# Poactuator_Power_Circuits.net
KiCad netlist of a schematic drawn in Altium Designer
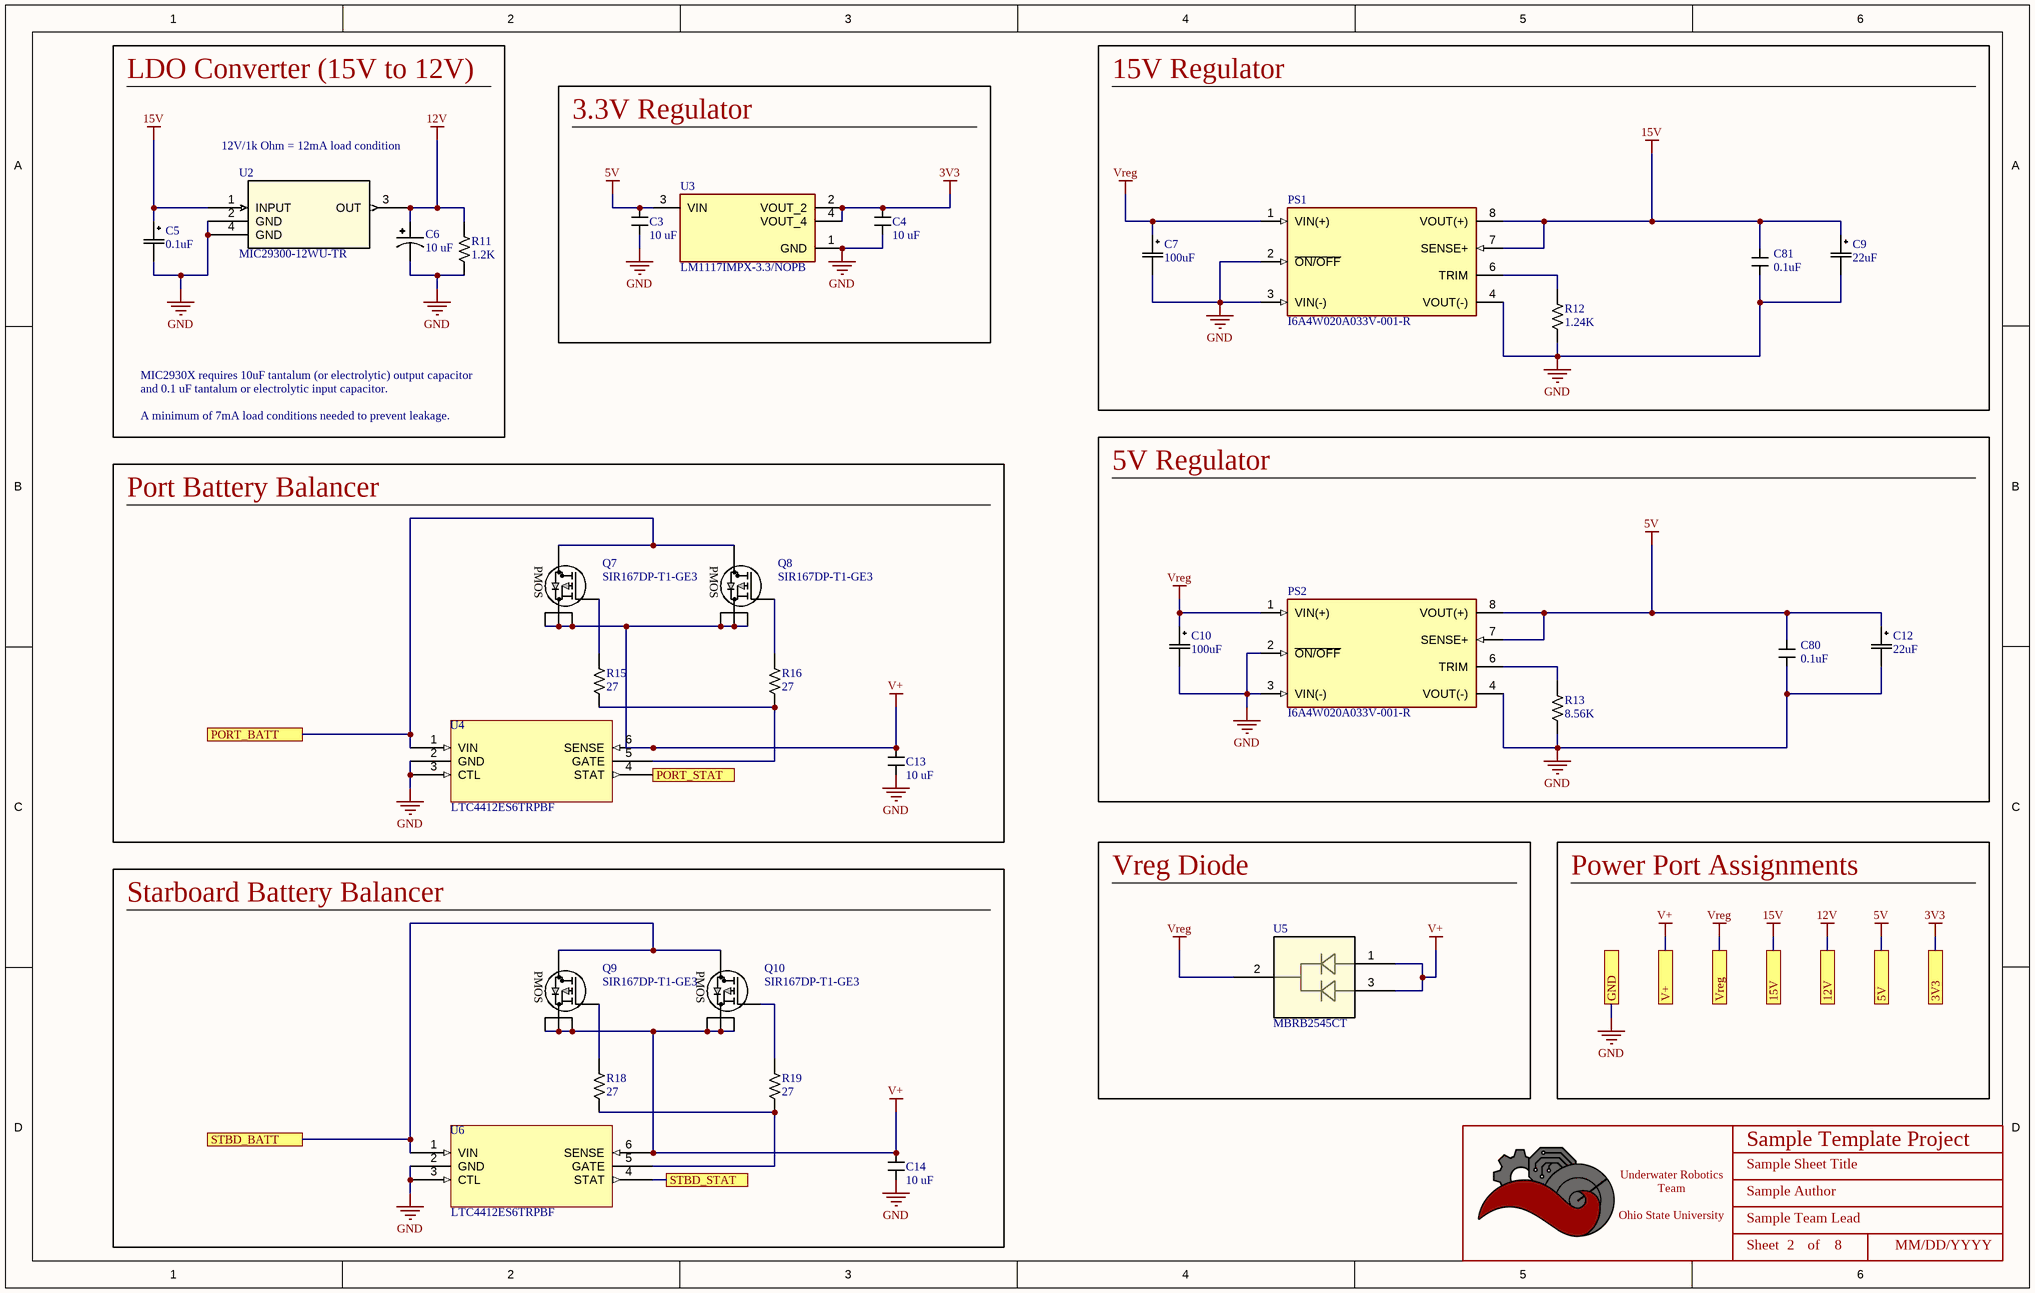
[diagram p0: Poactuator_Power_Circuits.SchDoc]

(export (version "E")
  (design (tool "Eeschema 10.0.6"))
  (components
    (comp (ref "C3")
      (value "10uF Ceramic 6.3V")
      (footprint "CAPACITOR_0603")
      (description "Cap 10uF 6.3V +/-20%\r\nCeramic 0603")
      (fields
        (field (name "TOLERANCE") "+/- 20%")
        (field (name "VOLTAGE") "6.3V")
        (field (name "VALUE (UF)") "10 uF")
        (field (name "MADE BY") "Flip B")
      )
      (libsource (lib "Capacitors") (part "CAPACITOR_10uF_0603"))
    )
    (comp (ref "C4")
      (value "10uF Ceramic 6.3V")
      (footprint "CAPACITOR_0603")
      (description "Cap 10uF 6.3V +/-20%\r\nCeramic 0603")
      (fields
        (field (name "TOLERANCE") "+/- 20%")
        (field (name "VOLTAGE") "6.3V")
        (field (name "VALUE (UF)") "10 uF")
        (field (name "MADE BY") "Flip B")
      )
      (libsource (lib "Capacitors") (part "CAPACITOR_10uF_0603"))
    )
    (comp (ref "C5")
      (value "0.1uF")
      (footprint "U2-D_NCH")
      (description "0.1 µF 35 V Aluminum Electrolytic Capacitors Radial, Can - SMD 7000 Hrs @ 105°C")
      (fields
        (field (name "MANUFACTURER_PART_NUMBER") "UCB1V0R1MCL1GS")
        (field (name "Comment") "0.1uF electrolytic 35 V")
        (field (name "COPYRIGHT") "Copyright (C) 2022 Ultra Librarian. All rights reserved.")
        (field (name "MADE BY") "Tyson Nguyen")
      )
      (libsource (lib "Capacitors") (part "CAP ALUM 0.1UF 20% 35V SMD"))
    )
    (comp (ref "C6")
      (value "10uF Tantalum 16V")
      (footprint "CAPACITOR_1206 - POLAR")
      (description "Cap 10uF 16V +/-20%\r\nTantalum 1206")
      (fields
        (field (name "TOLERANCE") "+/- 10%")
        (field (name "VOLTAGE") "16V")
        (field (name "VALUE (UF)") "10 uF")
        (field (name "MADE BY") "Dylan T")
      )
      (libsource (lib "Capacitors") (part "CAPACITOR_10uF_1206_Tantalum_1"))
    )
    (comp (ref "C7")
      (value "100uF")
      (footprint "PCAP_8x5.4-ELECT_NCA")
      (description "100 µF 35 V Aluminum Electrolytic Capacitors Radial, Can - SMD 1000 Hrs")
      (fields
        (field (name "MANUFACTURER_PART_NUMBER") "UCB1V0R1MCL1GS")
        (field (name "Comment") "100uF electrolytic 35 V")
        (field (name "COPYRIGHT") "Copyright (C) 2022 Ultra Librarian. All rights reserved.")
        (field (name "MADE BY") "Tyson Nguyen")
      )
      (libsource (lib "Capacitors") (part "CAP ALUM 100UF 20% 35V SMD"))
    )
    (comp (ref "C9")
      (value "22uF")
      (footprint "PCAP_8x5.4-ELECT_NCA")
      (description "22 µF 35 V Aluminum Electrolytic Capacitors Radial, Can - SMD 1000 Hrs")
      (fields
        (field (name "VOLTAGE") "35V")
        (field (name "Comment") "22uF electrolytic 35 V")
        (field (name "MADE BY") "Robert Pafford")
      )
      (libsource (lib "Capacitors") (part "CAP ALUM 22UF 20% 35V SMD"))
    )
    (comp (ref "C10")
      (value "100uF")
      (footprint "PCAP_8x5.4-ELECT_NCA")
      (description "100 µF 35 V Aluminum Electrolytic Capacitors Radial, Can - SMD 1000 Hrs")
      (fields
        (field (name "MANUFACTURER_PART_NUMBER") "UCB1V0R1MCL1GS")
        (field (name "Comment") "100uF electrolytic 35 V")
        (field (name "COPYRIGHT") "Copyright (C) 2022 Ultra Librarian. All rights reserved.")
        (field (name "MADE BY") "Tyson Nguyen")
      )
      (libsource (lib "Capacitors") (part "CAP ALUM 100UF 20% 35V SMD"))
    )
    (comp (ref "C12")
      (value "22uF")
      (footprint "PCAP_8x5.4-ELECT_NCA")
      (description "22 µF 35 V Aluminum Electrolytic Capacitors Radial, Can - SMD 1000 Hrs")
      (fields
        (field (name "VOLTAGE") "35V")
        (field (name "Comment") "22uF electrolytic 35 V")
        (field (name "MADE BY") "Robert Pafford")
      )
      (libsource (lib "Capacitors") (part "CAP ALUM 22UF 20% 35V SMD"))
    )
    (comp (ref "C13")
      (value "10uF Ceramic 25V")
      (footprint "CAPACITOR_1206")
      (description "Cap 10uF 25V +/-10%\r\nCeramic 1206")
      (fields
        (field (name "TOLERANCE") "+/- 10%")
        (field (name "VOLTAGE") "25V")
        (field (name "VALUE (UF)") "10 uF")
        (field (name "MADE BY") "Robert Pafford")
      )
      (libsource (lib "Capacitors") (part "CAPACITOR_10uF_1206"))
    )
    (comp (ref "C14")
      (value "10uF Ceramic 25V")
      (footprint "CAPACITOR_1206")
      (description "Cap 10uF 25V +/-10%\r\nCeramic 1206")
      (fields
        (field (name "TOLERANCE") "+/- 10%")
        (field (name "VOLTAGE") "25V")
        (field (name "VALUE (UF)") "10 uF")
        (field (name "MADE BY") "Robert Pafford")
      )
      (libsource (lib "Capacitors") (part "CAPACITOR_10uF_1206"))
    )
    (comp (ref "C80")
      (value "CL05A104KA5NNNC")
      (footprint "CL05A104KA5NNNC")
      (description "0.1 µF ±10% 25V Ceramic Capacitor X5R 0402 (1005 Metric)")
      (fields (field (name "CAPACITANCE") "0.1uF") (field (name "TOLERANCE") "+/- 10%"))
      (libsource (lib "Capacitors") (part "CAP CER 0.1UF 25V X5R 0402"))
    )
    (comp (ref "C81")
      (value "CL05A104KA5NNNC")
      (footprint "CL05A104KA5NNNC")
      (description "0.1 µF ±10% 25V Ceramic Capacitor X5R 0402 (1005 Metric)")
      (fields (field (name "CAPACITANCE") "0.1uF") (field (name "TOLERANCE") "+/- 10%"))
      (libsource (lib "Capacitors") (part "CAP CER 0.1UF 25V X5R 0402"))
    )
    (comp (ref "PS1")
      (value "I6A4W020A033V-001-R")
      (footprint "CONV_I6A4W020A033V-001-R")
      (description "Non-Isolated PoL Module DC DC Converter 1 Output 3.3 ~ 15V 20A 9V - 53V Input")
      (fields (field (name "MF") "TDK-Lambda Americas"))
      (libsource (lib "I6A4W020A033V-001-R") (part "I6A4W020A033V-001-R"))
    )
    (comp (ref "PS2")
      (value "I6A4W020A033V-001-R")
      (footprint "CONV_I6A4W020A033V-001-R")
      (description "Non-Isolated PoL Module DC DC Converter 1 Output 3.3 ~ 15V 20A 9V - 53V Input")
      (fields (field (name "MF") "TDK-Lambda Americas"))
      (libsource (lib "I6A4W020A033V-001-R") (part "I6A4W020A033V-001-R"))
    )
    (comp (ref "Q7")
      (value "SIR167DP-T1-GE3")
      (footprint "MOSFET_7DP-T1-GE3_VIS")
      (description "P-Channel 30 V 60A (Tc) 65.8W (Tc) Surface Mount PowerPAK® SO-8")
      (fields (field (name "COPYRIGHT") "Copyright (C) 2022 Ultra Librarian. All rights reserved."))
      (libsource (lib "Transistors") (part "SIR167DP-T1-GE3"))
    )
    (comp (ref "Q8")
      (value "SIR167DP-T1-GE3")
      (footprint "MOSFET_7DP-T1-GE3_VIS")
      (description "P-Channel 30 V 60A (Tc) 65.8W (Tc) Surface Mount PowerPAK® SO-8")
      (fields (field (name "COPYRIGHT") "Copyright (C) 2022 Ultra Librarian. All rights reserved."))
      (libsource (lib "Transistors") (part "SIR167DP-T1-GE3"))
    )
    (comp (ref "Q9")
      (value "SIR167DP-T1-GE3")
      (footprint "MOSFET_7DP-T1-GE3_VIS")
      (description "P-Channel 30 V 60A (Tc) 65.8W (Tc) Surface Mount PowerPAK® SO-8")
      (fields (field (name "COPYRIGHT") "Copyright (C) 2022 Ultra Librarian. All rights reserved."))
      (libsource (lib "Transistors") (part "SIR167DP-T1-GE3"))
    )
    (comp (ref "Q10")
      (value "SIR167DP-T1-GE3")
      (footprint "MOSFET_7DP-T1-GE3_VIS")
      (description "P-Channel 30 V 60A (Tc) 65.8W (Tc) Surface Mount PowerPAK® SO-8")
      (fields (field (name "COPYRIGHT") "Copyright (C) 2022 Ultra Librarian. All rights reserved."))
      (libsource (lib "Transistors") (part "SIR167DP-T1-GE3"))
    )
    (comp (ref "R11")
      (value "1.2k Ohm 5% 1/2W")
      (footprint "RESISTOR_0805")
      (description "RES 1.2k OHM 5% 1/2W 0805")
      (fields
        (field (name "TOLERANCE") "+/- 5%")
        (field (name "VALUE  (OHMS)") "1.2K")
        (field (name "MADE BY") "Robert Pafford")
      )
      (libsource (lib "Resistors") (part "RESISTOR_1.2K_0805"))
    )
    (comp (ref "R12")
      (value "RES 1.24K OHM 1% 1/10W 0603")
      (footprint "RESISTOR_0603")
      (description "1.24 kOhms ±1% 0.1W, 1/10W Chip Resistor 0603 (1608 Metric) Automotive AEC-Q200 Thick Film")
      (fields
        (field (name "TOLERANCE") "+/- 1%")
        (field (name "VALUE (OHMS)") "1.24K")
        (field (name "CREATED BY") "John Ulm")
        (field (name "VERIFIED BY") "*")
      )
      (libsource (lib "Resistors") (part "RESISTOR_1.24K_1%_0603"))
    )
    (comp (ref "R13")
      (value "RES 8.56K OHM 1% 1/16W 0402")
      (footprint "RESISTOR_0402")
      (fields
        (field (name "TOLERANCE") "+/- 1%")
        (field (name "VALUE (OHMS)") "8.56K")
        (field (name "MADE BY") "John Ulm")
        (field (name "VERIFIED BY") "*")
      )
      (libsource (lib "Resistors") (part "RESISTOR_8.56K_1%_0402"))
    )
    (comp (ref "R15")
      (value "27 Ohm 5% 1/8W")
      (footprint "RESISTOR_0603")
      (description "RES 27 OHM 5% 1/8W 0603")
      (fields
        (field (name "TOLERANCE") "+/- 5%")
        (field (name "VALUE  (OHMS)") "27")
        (field (name "MADE BY") "Robert Pafford")
      )
      (libsource (lib "Resistors") (part "RESISTOR_27_0603"))
    )
    (comp (ref "R16")
      (value "27 Ohm 5% 1/8W")
      (footprint "RESISTOR_0603")
      (description "RES 27 OHM 5% 1/8W 0603")
      (fields
        (field (name "TOLERANCE") "+/- 5%")
        (field (name "VALUE  (OHMS)") "27")
        (field (name "MADE BY") "Robert Pafford")
      )
      (libsource (lib "Resistors") (part "RESISTOR_27_0603"))
    )
    (comp (ref "R18")
      (value "27 Ohm 5% 1/8W")
      (footprint "RESISTOR_0603")
      (description "RES 27 OHM 5% 1/8W 0603")
      (fields
        (field (name "TOLERANCE") "+/- 5%")
        (field (name "VALUE  (OHMS)") "27")
        (field (name "MADE BY") "Robert Pafford")
      )
      (libsource (lib "Resistors") (part "RESISTOR_27_0603"))
    )
    (comp (ref "R19")
      (value "27 Ohm 5% 1/8W")
      (footprint "RESISTOR_0603")
      (description "RES 27 OHM 5% 1/8W 0603")
      (fields
        (field (name "TOLERANCE") "+/- 5%")
        (field (name "VALUE  (OHMS)") "27")
        (field (name "MADE BY") "Robert Pafford")
      )
      (libsource (lib "Resistors") (part "RESISTOR_27_0603"))
    )
    (comp (ref "U2")
      (value "MIC29300-12WU-TR")
      (footprint "TO-263-3_MCH")
      (description "Linear Voltage Regulator IC Positive Fixed 1 Output 3A TO-263-3")
      (fields (field (name "COPYRIGHT") "Copyright (C) 2022 Ultra Librarian. All rights reserved."))
      (libsource (lib "Converter") (part "MIC29300-12WU-TR"))
    )
    (comp (ref "U3")
      (value "LM1117IMPX-3.3/NOPB")
      (footprint "SOT-223-4")
      (description "800-mA 15-V linear voltage regulator 4-SOT-223 -40 to 125")
      (fields (field (name "MF") "Texas Instruments"))
      (libsource (lib "Integrated Circuits") (part "LM1117IMPX-3.3/NOPB"))
    )
    (comp (ref "U4")
      (value "LTC4412ES6TRPBF")
      (footprint "TSOT-23_S6")
      (description "OR Controller Source Selector Switch P-Channel 2:1 TSOT-23-6")
      (fields (field (name "MP") "LTC4412ES6#TRPBF") (field (name "MF") "Analog Devices"))
      (libsource (lib "Integrated Circuits") (part "LTC4412ES6TRPBF"))
    )
    (comp (ref "U5")
      (value "MBRB2545CT")
      (footprint "D2PAK_VIS")
      (description "Diode Array 1 Pair Common Cathode 45 V Surface Mount TO-263-3, D²Pak (2 Leads + Tab), TO-263AB")
      (fields (field (name "COPYRIGHT") "Copyright (C) 2023 Ultra Librarian. All rights reserved."))
      (libsource (lib "Diodes") (part "MBRB2545CT"))
    )
    (comp (ref "U6")
      (value "LTC4412ES6TRPBF")
      (footprint "TSOT-23_S6")
      (description "OR Controller Source Selector Switch P-Channel 2:1 TSOT-23-6")
      (fields (field (name "MP") "LTC4412ES6#TRPBF") (field (name "MF") "Analog Devices"))
      (libsource (lib "Integrated Circuits") (part "LTC4412ES6TRPBF"))
    )
  )
  (nets
    (net (code "1") (name "/PORT_BATT") (class "Default")
      (node (ref "Q7") (pin "D") (pinfunction "D_D") (pintype "passive"))
      (node (ref "Q8") (pin "D") (pinfunction "D_D") (pintype "passive"))
      (node (ref "U4") (pin "1") (pinfunction "VIN_1") (pintype "input"))
    )
    (net (code "2") (name "/PORT_STAT") (class "Default")
      (node (ref "U4") (pin "4") (pinfunction "STAT_4") (pintype "output"))
    )
    (net (code "3") (name "/STBD_BATT") (class "Default")
      (node (ref "Q10") (pin "D") (pinfunction "D_D") (pintype "passive"))
      (node (ref "Q9") (pin "D") (pinfunction "D_D") (pintype "passive"))
      (node (ref "U6") (pin "1") (pinfunction "VIN_1") (pintype "input"))
    )
    (net (code "4") (name "/STBD_STAT") (class "Default")
      (node (ref "U6") (pin "4") (pinfunction "STAT_4") (pintype "output"))
    )
    (net (code "5") (name "3V3") (class "Default")
      (node (ref "C4") (pin "1") (pinfunction "1_1") (pintype "passive"))
      (node (ref "U3") (pin "2") (pinfunction "VOUT_2_2") (pintype "power_in"))
      (node (ref "U3") (pin "4") (pinfunction "VOUT_4_4") (pintype "power_in"))
    )
    (net (code "6") (name "5V") (class "Default")
      (node (ref "C12") (pin "1") (pinfunction "1_1") (pintype "passive"))
      (node (ref "C3") (pin "1") (pinfunction "1_1") (pintype "passive"))
      (node (ref "C80") (pin "1") (pinfunction "1_1") (pintype "passive"))
      (node (ref "PS2") (pin "7") (pinfunction "SENSE+_7") (pintype "input"))
      (node (ref "PS2") (pin "8") (pinfunction "VOUT(+)_8") (pintype "power_in"))
      (node (ref "U3") (pin "3") (pinfunction "VIN_3") (pintype "power_in"))
    )
    (net (code "7") (name "12V") (class "Default")
      (node (ref "C6") (pin "1") (pintype "passive"))
      (node (ref "R11") (pin "1") (pinfunction "1_1") (pintype "passive"))
      (node (ref "U2") (pin "3") (pinfunction "OUT_3") (pintype "output"))
    )
    (net (code "8") (name "15V") (class "Default")
      (node (ref "C5") (pin "1") (pinfunction "1_1") (pintype "passive"))
      (node (ref "C81") (pin "1") (pinfunction "1_1") (pintype "passive"))
      (node (ref "C9") (pin "1") (pinfunction "1_1") (pintype "passive"))
      (node (ref "PS1") (pin "7") (pinfunction "SENSE+_7") (pintype "input"))
      (node (ref "PS1") (pin "8") (pinfunction "VOUT(+)_8") (pintype "power_in"))
      (node (ref "U2") (pin "1") (pinfunction "INPUT_1") (pintype "input"))
    )
    (net (code "9") (name "GND") (class "Default")
      (node (ref "C10") (pin "2") (pinfunction "2_2") (pintype "passive"))
      (node (ref "C12") (pin "2") (pinfunction "2_2") (pintype "passive"))
      (node (ref "C13") (pin "2") (pinfunction "2_2") (pintype "passive"))
      (node (ref "C14") (pin "2") (pinfunction "2_2") (pintype "passive"))
      (node (ref "C3") (pin "2") (pinfunction "2_2") (pintype "passive"))
      (node (ref "C4") (pin "2") (pinfunction "2_2") (pintype "passive"))
      (node (ref "C5") (pin "2") (pinfunction "2_2") (pintype "passive"))
      (node (ref "C6") (pin "2") (pintype "passive"))
      (node (ref "C7") (pin "2") (pinfunction "2_2") (pintype "passive"))
      (node (ref "C80") (pin "2") (pinfunction "2_2") (pintype "passive"))
      (node (ref "C81") (pin "2") (pinfunction "2_2") (pintype "passive"))
      (node (ref "C9") (pin "2") (pinfunction "2_2") (pintype "passive"))
      (node (ref "PS1") (pin "2") (pinfunction "~{ON/OFF}_2") (pintype "input"))
      (node (ref "PS1") (pin "3") (pinfunction "VIN(-)_3") (pintype "input"))
      (node (ref "PS1") (pin "4") (pinfunction "VOUT(-)_4") (pintype "power_in"))
      (node (ref "PS2") (pin "2") (pinfunction "~{ON/OFF}_2") (pintype "input"))
      (node (ref "PS2") (pin "3") (pinfunction "VIN(-)_3") (pintype "input"))
      (node (ref "PS2") (pin "4") (pinfunction "VOUT(-)_4") (pintype "power_in"))
      (node (ref "R11") (pin "2") (pinfunction "2_2") (pintype "passive"))
      (node (ref "R12") (pin "2") (pinfunction "2_2") (pintype "passive"))
      (node (ref "R13") (pin "2") (pinfunction "2_2") (pintype "passive"))
      (node (ref "U2") (pin "2") (pinfunction "GND_2") (pintype "power_in"))
      (node (ref "U2") (pin "4") (pinfunction "GND_4") (pintype "power_in"))
      (node (ref "U3") (pin "1") (pinfunction "GND_1") (pintype "power_in"))
      (node (ref "U4") (pin "2") (pinfunction "GND_2") (pintype "power_in"))
      (node (ref "U4") (pin "3") (pinfunction "CTL_3") (pintype "input"))
      (node (ref "U6") (pin "2") (pinfunction "GND_2") (pintype "power_in"))
      (node (ref "U6") (pin "3") (pinfunction "CTL_3") (pintype "input"))
    )
    (net (code "10") (name "Net-(PS1-TRIM)") (class "Default")
      (node (ref "PS1") (pin "6") (pinfunction "TRIM_6") (pintype "passive"))
      (node (ref "R12") (pin "1") (pinfunction "1_1") (pintype "passive"))
    )
    (net (code "11") (name "Net-(PS2-TRIM)") (class "Default")
      (node (ref "PS2") (pin "6") (pinfunction "TRIM_6") (pintype "passive"))
      (node (ref "R13") (pin "1") (pinfunction "1_1") (pintype "passive"))
    )
    (net (code "12") (name "Net-(Q7-G)") (class "Default")
      (node (ref "Q7") (pin "4") (pinfunction "G_4") (pintype "passive"))
      (node (ref "R15") (pin "1") (pinfunction "1_1") (pintype "passive"))
    )
    (net (code "13") (name "Net-(Q8-G)") (class "Default")
      (node (ref "Q8") (pin "4") (pinfunction "G_4") (pintype "passive"))
      (node (ref "R16") (pin "1") (pinfunction "1_1") (pintype "passive"))
    )
    (net (code "14") (name "Net-(Q9-G)") (class "Default")
      (node (ref "Q9") (pin "4") (pinfunction "G_4") (pintype "passive"))
      (node (ref "R18") (pin "1") (pinfunction "1_1") (pintype "passive"))
    )
    (net (code "15") (name "Net-(Q10-G)") (class "Default")
      (node (ref "Q10") (pin "4") (pinfunction "G_4") (pintype "passive"))
      (node (ref "R19") (pin "1") (pinfunction "1_1") (pintype "passive"))
    )
    (net (code "16") (name "Net-(U4-GATE)") (class "Default")
      (node (ref "R15") (pin "2") (pinfunction "2_2") (pintype "passive"))
      (node (ref "R16") (pin "2") (pinfunction "2_2") (pintype "passive"))
      (node (ref "U4") (pin "5") (pinfunction "GATE_5") (pintype "passive"))
    )
    (net (code "17") (name "Net-(U6-GATE)") (class "Default")
      (node (ref "R18") (pin "2") (pinfunction "2_2") (pintype "passive"))
      (node (ref "R19") (pin "2") (pinfunction "2_2") (pintype "passive"))
      (node (ref "U6") (pin "5") (pinfunction "GATE_5") (pintype "passive"))
    )
    (net (code "18") (name "V+") (class "Default")
      (node (ref "C13") (pin "1") (pinfunction "1_1") (pintype "passive"))
      (node (ref "C14") (pin "1") (pinfunction "1_1") (pintype "passive"))
      (node (ref "Q10") (pin "1") (pinfunction "S_1") (pintype "passive"))
      (node (ref "Q10") (pin "2") (pinfunction "S_2") (pintype "passive"))
      (node (ref "Q10") (pin "3") (pinfunction "S_3") (pintype "passive"))
      (node (ref "Q7") (pin "1") (pinfunction "S_1") (pintype "passive"))
      (node (ref "Q7") (pin "2") (pinfunction "S_2") (pintype "passive"))
      (node (ref "Q7") (pin "3") (pinfunction "S_3") (pintype "passive"))
      (node (ref "Q8") (pin "1") (pinfunction "S_1") (pintype "passive"))
      (node (ref "Q8") (pin "2") (pinfunction "S_2") (pintype "passive"))
      (node (ref "Q8") (pin "3") (pinfunction "S_3") (pintype "passive"))
      (node (ref "Q9") (pin "1") (pinfunction "S_1") (pintype "passive"))
      (node (ref "Q9") (pin "2") (pinfunction "S_2") (pintype "passive"))
      (node (ref "Q9") (pin "3") (pinfunction "S_3") (pintype "passive"))
      (node (ref "U4") (pin "6") (pinfunction "SENSE_6") (pintype "input"))
      (node (ref "U5") (pin "1") (pinfunction "1_1") (pintype "passive"))
      (node (ref "U5") (pin "3") (pinfunction "3_3") (pintype "passive"))
      (node (ref "U6") (pin "6") (pinfunction "SENSE_6") (pintype "input"))
    )
    (net (code "19") (name "Vreg") (class "Default")
      (node (ref "C10") (pin "1") (pinfunction "1_1") (pintype "passive"))
      (node (ref "C7") (pin "1") (pinfunction "1_1") (pintype "passive"))
      (node (ref "PS1") (pin "1") (pinfunction "VIN(+)_1") (pintype "input"))
      (node (ref "PS2") (pin "1") (pinfunction "VIN(+)_1") (pintype "input"))
      (node (ref "U5") (pin "2") (pinfunction "2_2") (pintype "passive"))
    )
  )
)
